# SCH_Slime_Wemos.net
KiCad netlist of a schematic drawn in EasyEDA
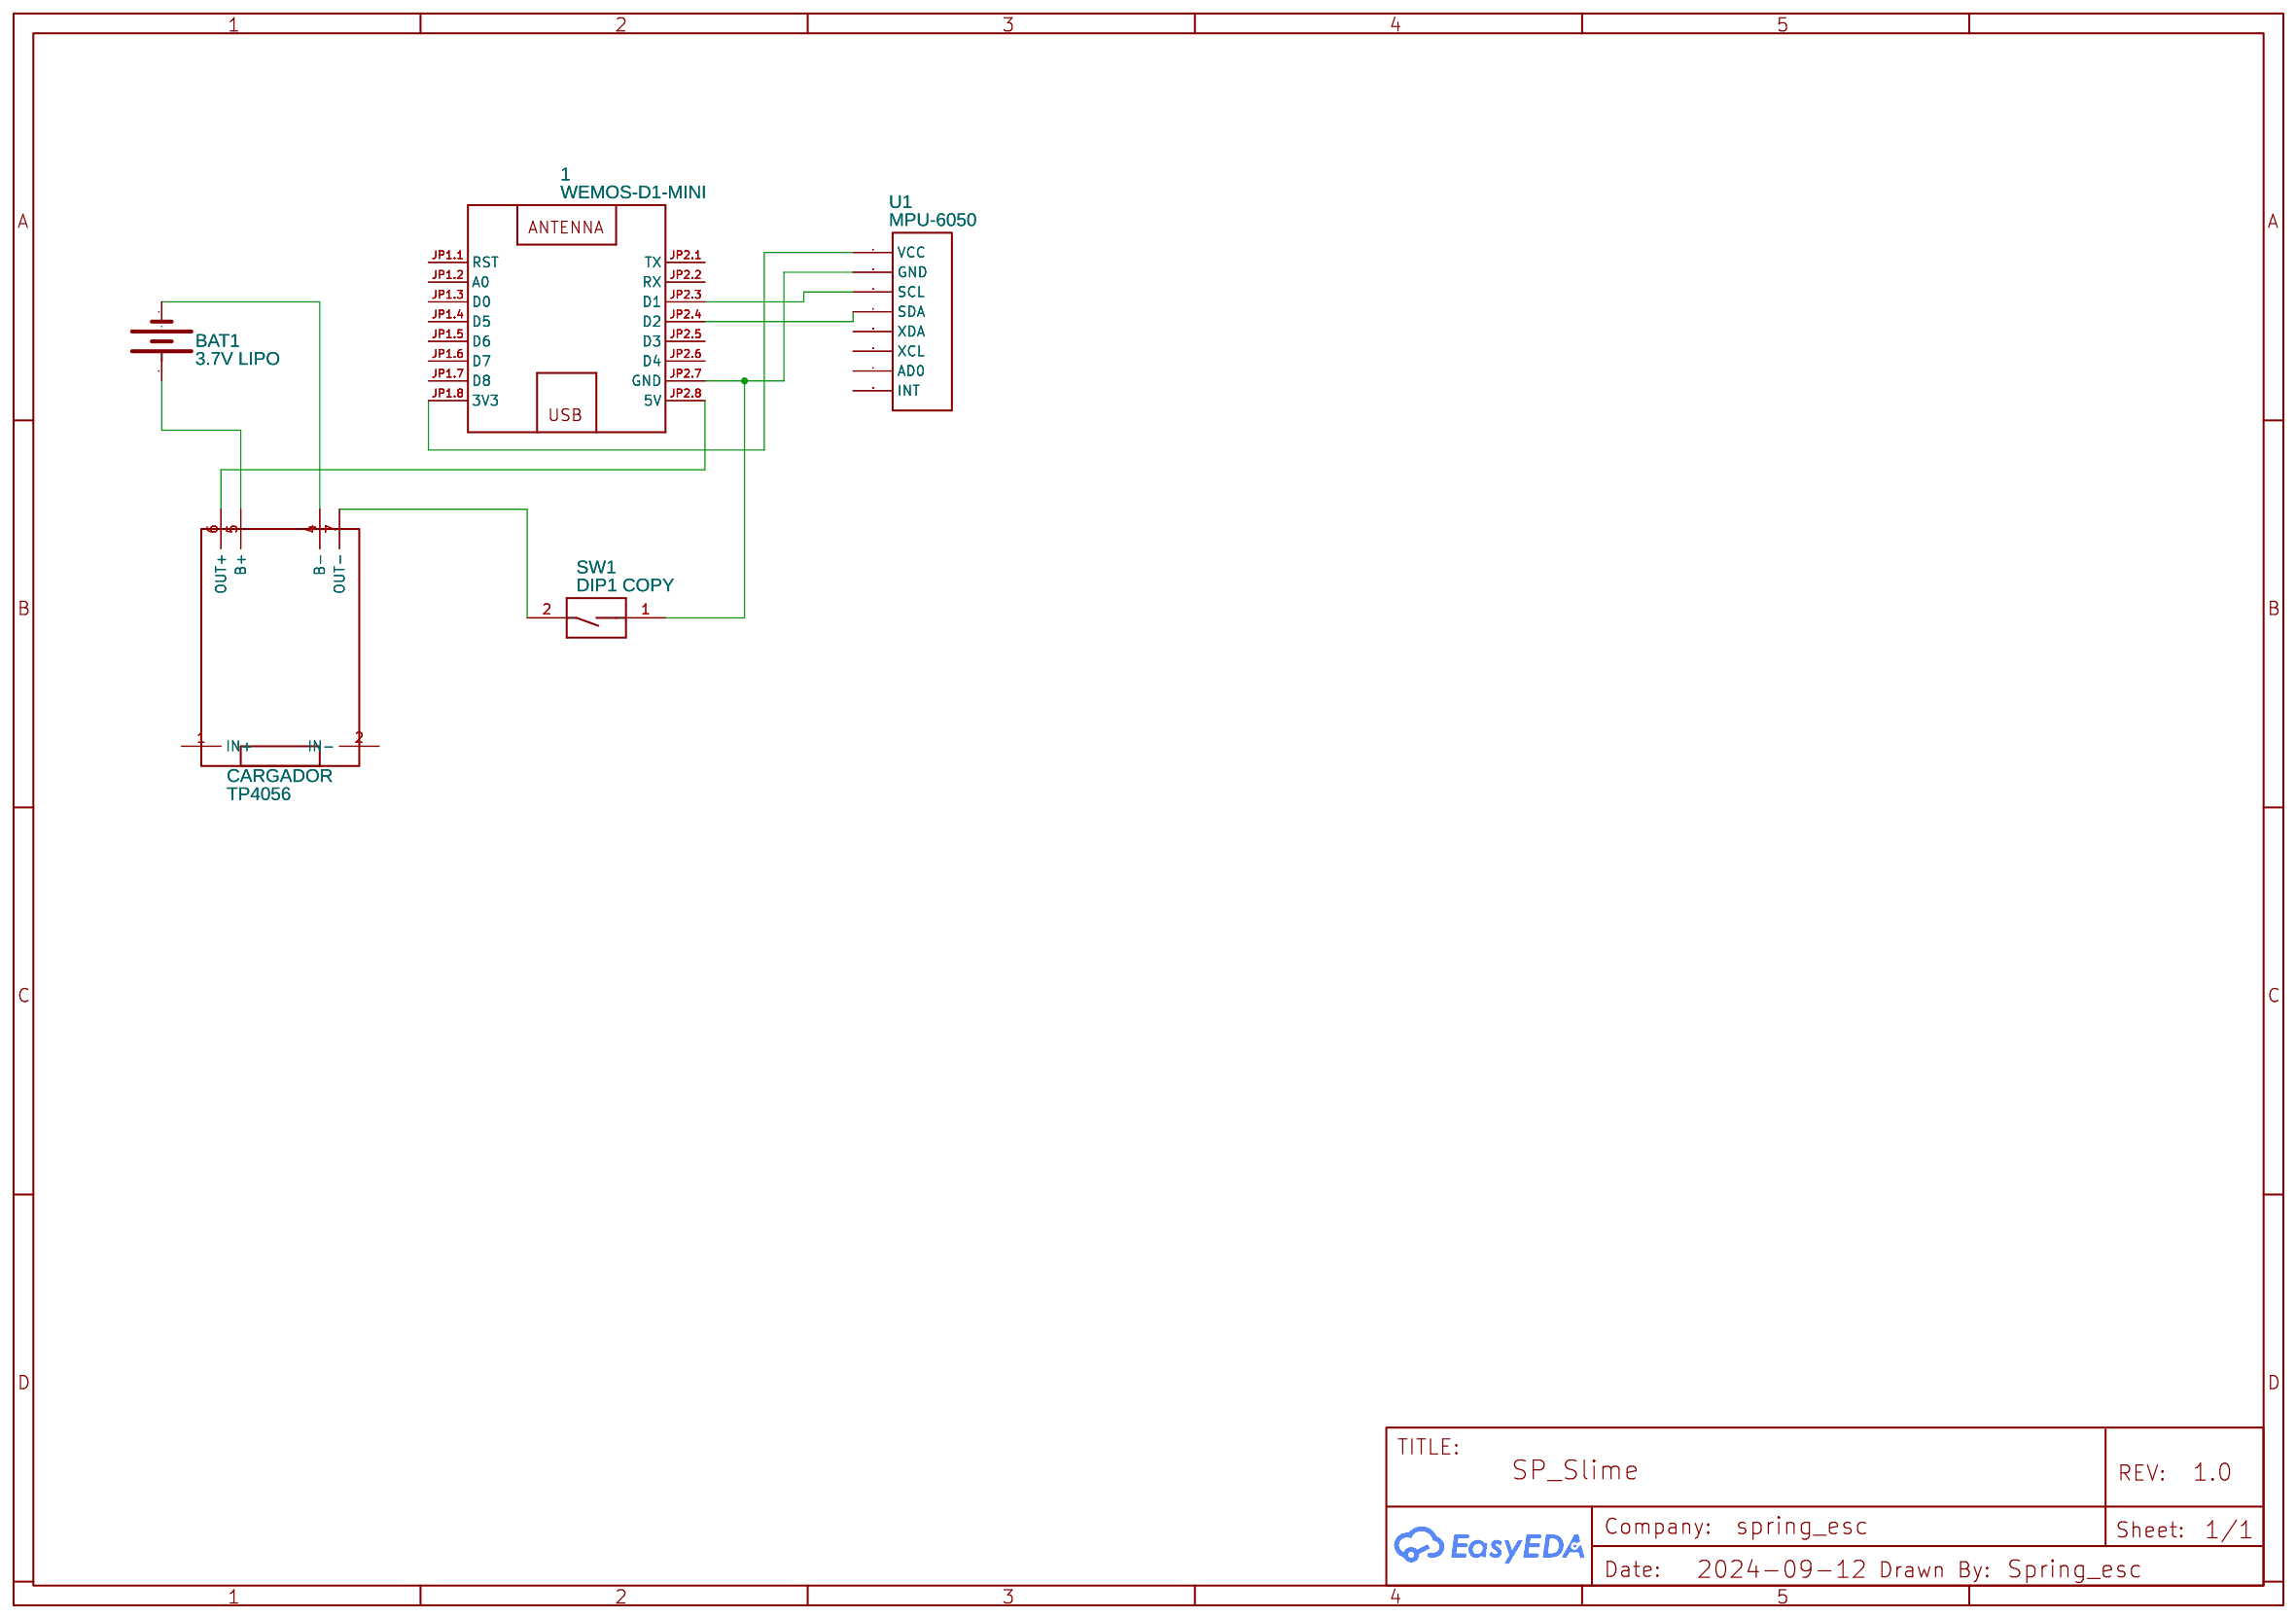
[diagram p0: schematic sheet]

(export (version "E")
  (design (tool "Eeschema 10.0.6"))
  (components
    (comp (ref "1") (value "WEMOS-D1-MINI") (libsource (lib "") (part "WEMOS-D1-MINI")))
    (comp (ref "BAT1") (value "3.7V LIPO") (libsource (lib "") (part "3.7V LIPO")))
    (comp (ref "CARGADOR")
      (value "TP4056")
      (fields (field (name "Manufacturer Part") "TP4056-protect"))
      (libsource (lib "") (part "TP4056"))
    )
    (comp (ref "SW1")
      (value "DIP1 COPY")
      (fields
        (field (name "Manufacturer Part") "A6TN-1101")
        (field (name "Manufacturer") "Omron Electronics Inc-EMC Div")
      )
      (libsource (lib "") (part "DIP1 COPY"))
    )
    (comp (ref "U1") (value "MPU-6050") (libsource (lib "") (part "MPU-6050")))
  )
  (nets
    (net (code "1") (name "Net-(1-3V3)") (class "Default")
      (node (ref "1") (pin "JP1.8") (pinfunction "3V3_JP1.8") (pintype "bidirectional"))
      (node (ref "U1") (pin "1") (pinfunction "VCC_1") (pintype "unspecified"))
    )
    (net (code "2") (name "Net-(1-5V)") (class "Default")
      (node (ref "1") (pin "JP2.8") (pinfunction "5V_JP2.8") (pintype "bidirectional"))
      (node (ref "CARGADOR") (pin "6") (pinfunction "OUT+_6") (pintype "unspecified"))
    )
    (net (code "3") (name "Net-(1-D1)") (class "Default")
      (node (ref "1") (pin "JP2.3") (pinfunction "D1_JP2.3") (pintype "bidirectional"))
      (node (ref "U1") (pin "3") (pinfunction "SCL_3") (pintype "unspecified"))
    )
    (net (code "4") (name "Net-(1-D2)") (class "Default")
      (node (ref "1") (pin "JP2.4") (pinfunction "D2_JP2.4") (pintype "bidirectional"))
      (node (ref "U1") (pin "4") (pinfunction "SDA_4") (pintype "unspecified"))
    )
    (net (code "5") (name "Net-(1-GND)") (class "Default")
      (node (ref "1") (pin "JP2.7") (pinfunction "GND_JP2.7") (pintype "bidirectional"))
      (node (ref "SW1") (pin "1") (pinfunction "1_1") (pintype "unspecified"))
      (node (ref "U1") (pin "2") (pinfunction "GND_2") (pintype "unspecified"))
    )
    (net (code "6") (name "Net-(CARGADOR-B+)") (class "Default")
      (node (ref "BAT1") (pin "+") (pinfunction "+_+") (pintype "passive"))
      (node (ref "CARGADOR") (pin "5") (pinfunction "B+_5") (pintype "unspecified"))
    )
    (net (code "7") (name "Net-(CARGADOR-B-)") (class "Default")
      (node (ref "BAT1") (pin "-") (pinfunction "-_-") (pintype "passive"))
      (node (ref "CARGADOR") (pin "4") (pinfunction "B-_4") (pintype "unspecified"))
    )
    (net (code "8") (name "Net-(CARGADOR-OUT-)") (class "Default")
      (node (ref "CARGADOR") (pin "7") (pinfunction "OUT-_7") (pintype "unspecified"))
      (node (ref "SW1") (pin "2") (pinfunction "2_2") (pintype "unspecified"))
    )
    (net (code "9") (name "unconnected-(1-A0-PadJP1.2)") (class "Default")
      (node (ref "1") (pin "JP1.2") (pinfunction "A0_JP1.2") (pintype "bidirectional"))
    )
    (net (code "10") (name "unconnected-(1-D0-PadJP1.3)") (class "Default")
      (node (ref "1") (pin "JP1.3") (pinfunction "D0_JP1.3") (pintype "bidirectional"))
    )
    (net (code "11") (name "unconnected-(1-D3-PadJP2.5)") (class "Default")
      (node (ref "1") (pin "JP2.5") (pinfunction "D3_JP2.5") (pintype "bidirectional"))
    )
    (net (code "12") (name "unconnected-(1-D4-PadJP2.6)") (class "Default")
      (node (ref "1") (pin "JP2.6") (pinfunction "D4_JP2.6") (pintype "bidirectional"))
    )
    (net (code "13") (name "unconnected-(1-D5-PadJP1.4)") (class "Default")
      (node (ref "1") (pin "JP1.4") (pinfunction "D5_JP1.4") (pintype "bidirectional"))
    )
    (net (code "14") (name "unconnected-(1-D6-PadJP1.5)") (class "Default")
      (node (ref "1") (pin "JP1.5") (pinfunction "D6_JP1.5") (pintype "bidirectional"))
    )
    (net (code "15") (name "unconnected-(1-D7-PadJP1.6)") (class "Default")
      (node (ref "1") (pin "JP1.6") (pinfunction "D7_JP1.6") (pintype "bidirectional"))
    )
    (net (code "16") (name "unconnected-(1-D8-PadJP1.7)") (class "Default")
      (node (ref "1") (pin "JP1.7") (pinfunction "D8_JP1.7") (pintype "bidirectional"))
    )
    (net (code "17") (name "unconnected-(1-RST-PadJP1.1)") (class "Default")
      (node (ref "1") (pin "JP1.1") (pinfunction "RST_JP1.1") (pintype "bidirectional"))
    )
    (net (code "18") (name "unconnected-(1-RX-PadJP2.2)") (class "Default")
      (node (ref "1") (pin "JP2.2") (pinfunction "RX_JP2.2") (pintype "bidirectional"))
    )
    (net (code "19") (name "unconnected-(1-TX-PadJP2.1)") (class "Default")
      (node (ref "1") (pin "JP2.1") (pinfunction "TX_JP2.1") (pintype "bidirectional"))
    )
    (net (code "20") (name "unconnected-(CARGADOR-IN+-Pad1)") (class "Default")
      (node (ref "CARGADOR") (pin "1") (pinfunction "IN+_1") (pintype "unspecified"))
    )
    (net (code "21") (name "unconnected-(CARGADOR-IN--Pad2)") (class "Default")
      (node (ref "CARGADOR") (pin "2") (pinfunction "IN-_2") (pintype "unspecified"))
    )
    (net (code "22") (name "unconnected-(U1-AD0-Pad7)") (class "Default")
      (node (ref "U1") (pin "7") (pinfunction "AD0_7") (pintype "unspecified"))
    )
    (net (code "23") (name "unconnected-(U1-INT-Pad8)") (class "Default")
      (node (ref "U1") (pin "8") (pinfunction "INT_8") (pintype "unspecified"))
    )
    (net (code "24") (name "unconnected-(U1-XCL-Pad6)") (class "Default")
      (node (ref "U1") (pin "6") (pinfunction "XCL_6") (pintype "unspecified"))
    )
    (net (code "25") (name "unconnected-(U1-XDA-Pad5)") (class "Default")
      (node (ref "U1") (pin "5") (pinfunction "XDA_5") (pintype "unspecified"))
    )
  )
)
